# I2C.net
KiCad netlist of a schematic drawn in Altium Designer
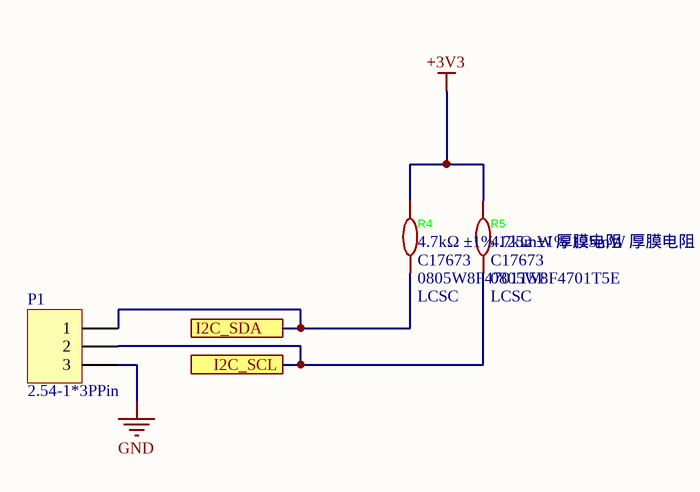
[diagram p0: I2C.SchDoc]

(export (version "E")
  (design (tool "Eeschema 10.0.6"))
  (components
    (comp (ref "P1")
      (value "2.54-1*3PPin")
      (footprint "HDR1X3")
      (fields (field (name "PUBLISHER") "Altium Limited"))
      (libsource (lib "Miscellaneous Connectors") (part "Header 3"))
    )
    (comp (ref "R4")
      (value "4.7kΩ")
      (footprint "R0805")
      (fields
        (field (name "MANUFACTURER") "UNI-ROYAL(厚声)")
        (field (name "TOLERANCE") "±1%")
        (field (name "LCSC PART NAME") "4.7kΩ ±1% 125mW 厚膜电阻")
        (field (name "SUPPLIER PART") "C17673")
        (field (name "MANUFACTURER PART") "0805W8F4701T5E")
        (field (name "SUPPLIER") "LCSC")
      )
      (libsource (lib "RES_4.7k_0805W") (part "0805W8F4701T5E"))
    )
    (comp (ref "R5")
      (value "4.7kΩ")
      (footprint "R0805")
      (fields
        (field (name "MANUFACTURER") "UNI-ROYAL(厚声)")
        (field (name "TOLERANCE") "±1%")
        (field (name "LCSC PART NAME") "4.7kΩ ±1% 125mW 厚膜电阻")
        (field (name "SUPPLIER PART") "C17673")
        (field (name "MANUFACTURER PART") "0805W8F4701T5E")
        (field (name "SUPPLIER") "LCSC")
      )
      (libsource (lib "RES_4.7k_0805W") (part "0805W8F4701T5E"))
    )
  )
  (nets
    (net (code "1") (name "+3V3") (class "Default")
      (node (ref "R4") (pin "2") (pinfunction "2_2") (pintype "passive"))
      (node (ref "R5") (pin "2") (pinfunction "2_2") (pintype "passive"))
    )
    (net (code "2") (name "/I2C_SCL") (class "Default")
      (node (ref "P1") (pin "2") (pinfunction "2_2") (pintype "passive"))
      (node (ref "R5") (pin "1") (pinfunction "1_1") (pintype "passive"))
    )
    (net (code "3") (name "/I2C_SDA") (class "Default")
      (node (ref "P1") (pin "1") (pinfunction "1_1") (pintype "passive"))
      (node (ref "R4") (pin "1") (pinfunction "1_1") (pintype "passive"))
    )
    (net (code "4") (name "GND") (class "Default")
      (node (ref "P1") (pin "3") (pinfunction "3_3") (pintype "passive"))
    )
  )
)
